# 4_Sensors.net
KiCad netlist of a schematic drawn in Altium Designer
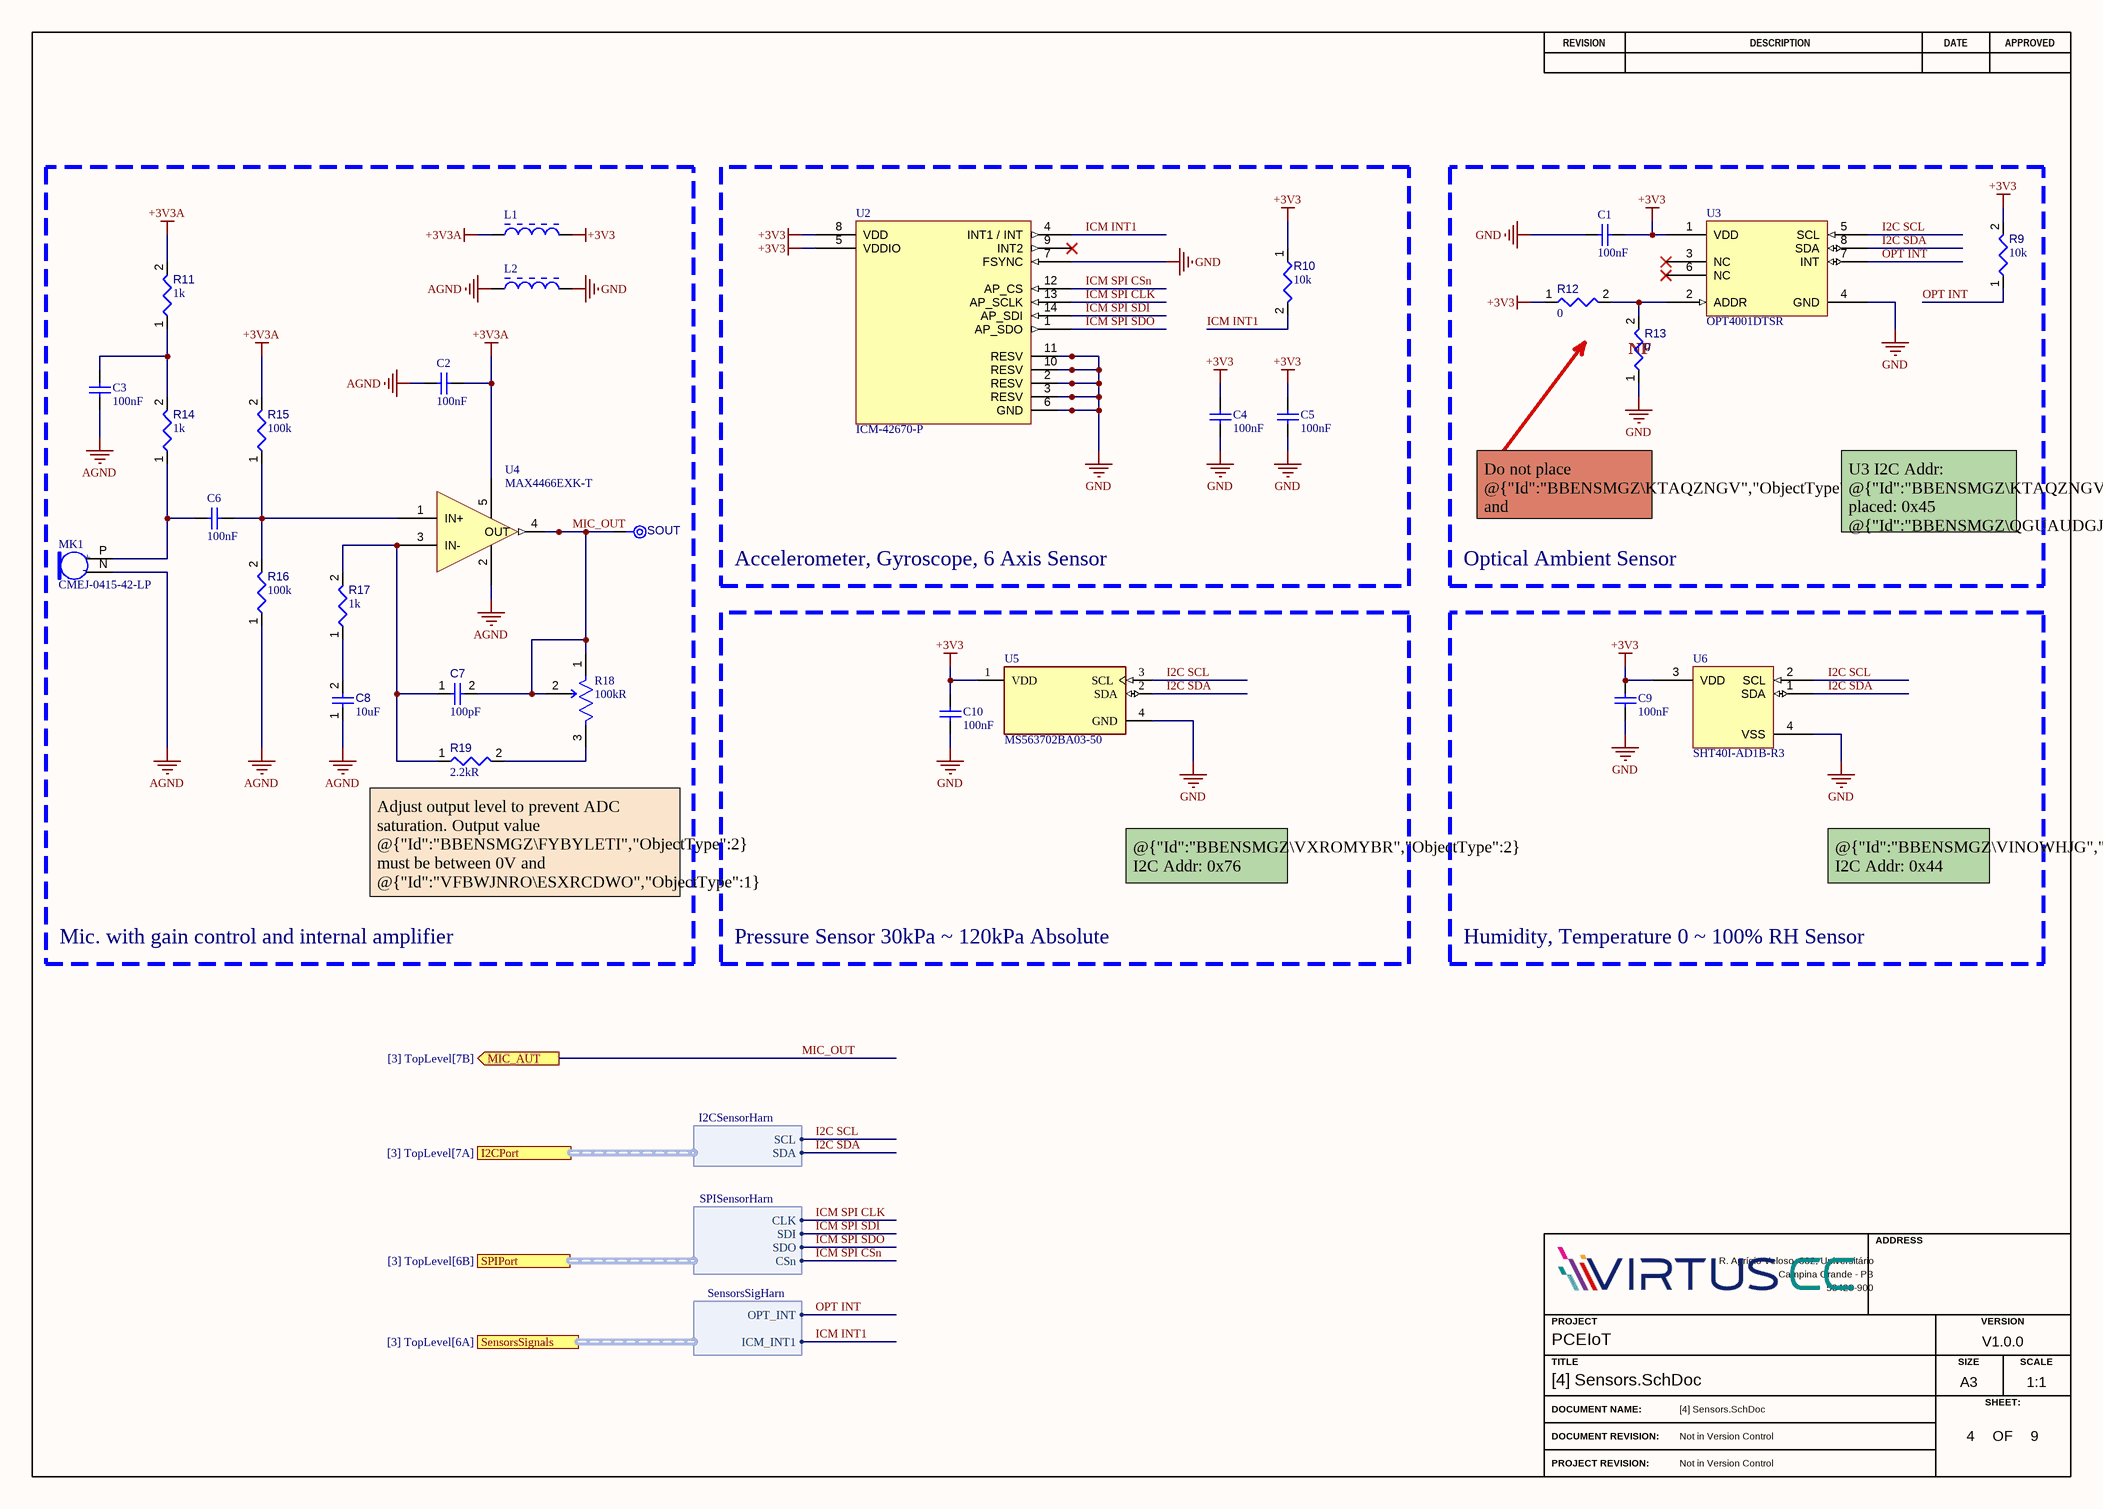
[diagram p0: [4] Sensors.SchDoc]

(export (version "E")
  (design (tool "Eeschema 10.0.6"))
  (components
    (comp (ref "C1")
      (value "100nF")
      (footprint "CAPC0603(1608)100_L")
      (description "Multilayer Ceramic Capacitor, 0.1 uF, 16 V, ± 20%, X7R, 0603 [1608 Metric]")
      (fields (field (name "TOLERANCE") "20%") (field (name "Comment") "VJ0603Y104MXJCW1BC"))
      (libsource (lib "UFCG - Universidade Federal de Campina Grande") (part "CAP"))
    )
    (comp (ref "C2")
      (value "100nF")
      (footprint "CAPC0603(1608)100_L")
      (description "Multilayer Ceramic Capacitor, 0.1 uF, 16 V, ± 20%, X7R, 0603 [1608 Metric]")
      (fields (field (name "TOLERANCE") "20%") (field (name "Comment") "VJ0603Y104MXJCW1BC"))
      (libsource (lib "UFCG - Universidade Federal de Campina Grande") (part "CAP"))
    )
    (comp (ref "C3")
      (value "100nF")
      (footprint "CAPC0603(1608)100_L")
      (description "Multilayer Ceramic Capacitor, 0.1 uF, 16 V, ± 20%, X7R, 0603 [1608 Metric]")
      (fields (field (name "TOLERANCE") "20%") (field (name "Comment") "VJ0603Y104MXJCW1BC"))
      (libsource (lib "UFCG - Universidade Federal de Campina Grande") (part "CAP"))
    )
    (comp (ref "C4")
      (value "100nF")
      (footprint "CAPC0603(1608)100_L")
      (description "Multilayer Ceramic Capacitor, 0.1 uF, 16 V, ± 20%, X7R, 0603 [1608 Metric]")
      (fields (field (name "TOLERANCE") "20%") (field (name "Comment") "VJ0603Y104MXJCW1BC"))
      (libsource (lib "UFCG - Universidade Federal de Campina Grande") (part "CAP"))
    )
    (comp (ref "C5")
      (value "100nF")
      (footprint "CAPC0603(1608)100_L")
      (description "Multilayer Ceramic Capacitor, 0.1 uF, 16 V, ± 20%, X7R, 0603 [1608 Metric]")
      (fields (field (name "TOLERANCE") "20%") (field (name "Comment") "VJ0603Y104MXJCW1BC"))
      (libsource (lib "UFCG - Universidade Federal de Campina Grande") (part "CAP"))
    )
    (comp (ref "C6")
      (value "100nF")
      (footprint "CAPC0603(1608)100_L")
      (description "Multilayer Ceramic Capacitor, 0.1 uF, 16 V, ± 20%, X7R, 0603 [1608 Metric]")
      (fields (field (name "TOLERANCE") "20%") (field (name "Comment") "VJ0603Y104MXJCW1BC"))
      (libsource (lib "UFCG - Universidade Federal de Campina Grande") (part "CAP"))
    )
    (comp (ref "C7")
      (value "100pF")
      (footprint "CAPC0603(1608)100_L")
      (description "Multilayer Ceramic Capacitor, 100 pF, 50 V, ï¿½ 10%, C0G (NP0), 0603 [1608 Metric]")
      (fields (field (name "TOLERANCE") "10%") (field (name "Comment") "C0603C101K5GACTU"))
      (libsource (lib "UFCG - Universidade Federal de Campina Grande") (part "CAP-NP-2"))
    )
    (comp (ref "C8")
      (value "10uF")
      (footprint "CAPC0603(1608)100_L")
      (description "Multilayer Ceramic Capacitor, 10 uF, 6.3 V, ± 20%, X5R, 0603 [1608 Metric]")
      (fields (field (name "TOLERANCE") "20%") (field (name "Comment") "GRM188R60J106ME47D"))
      (libsource (lib "UFCG - Universidade Federal de Campina Grande") (part "CAP-NP-2"))
    )
    (comp (ref "C9")
      (value "100nF")
      (footprint "CAPC0603(1608)100_L")
      (description "Multilayer Ceramic Capacitor, 0.1 uF, 16 V, ± 20%, X7R, 0603 [1608 Metric]")
      (fields (field (name "TOLERANCE") "20%") (field (name "Comment") "VJ0603Y104MXJCW1BC"))
      (libsource (lib "UFCG - Universidade Federal de Campina Grande") (part "CAP"))
    )
    (comp (ref "C10")
      (value "100nF")
      (footprint "CAPC0603(1608)100_L")
      (description "Multilayer Ceramic Capacitor, 0.1 uF, 16 V, ± 20%, X7R, 0603 [1608 Metric]")
      (fields (field (name "TOLERANCE") "20%") (field (name "Comment") "VJ0603Y104MXJCW1BC"))
      (libsource (lib "UFCG - Universidade Federal de Campina Grande") (part "CAP"))
    )
    (comp (ref "L1")
      (value "BLM21PG331SN1D")
      (footprint "INDC2013X105X50ML20T20")
      (fields (field (name "MANUFACTURER") "Murata") (field (name "TOLERANCE") "25%"))
      (libsource (lib "UFCG - Universidade Federal de Campina Grande") (part "IND-FB-2"))
    )
    (comp (ref "L2")
      (value "BLM21PG331SN1D")
      (footprint "INDC2013X105X50ML20T20")
      (fields (field (name "MANUFACTURER") "Murata") (field (name "TOLERANCE") "25%"))
      (libsource (lib "UFCG - Universidade Federal de Campina Grande") (part "IND-FB-2"))
    )
    (comp (ref "MK1")
      (value "CMEJ-0415-42-LP")
      (footprint "MIC_CMEJ-0415-42-LP")
      (description "4.0 mm, Omnidirectional, PCB Mount, 2.0 Vdc, Elecret Condenser Microphone")
      (fields (field (name "MF") "{'manufacturer': u'CUI'}"))
      (libsource (lib "UFCG - Universidade Federal de Campina Grande") (part "CMEJ-0415-42-LP"))
    )
    (comp (ref "R9")
      (value "10k")
      (footprint "RESC0603(1608)_L")
      (description "Chip Resistor, 10 KOhm, +/- 1%, 01 W, -55 to 155 degC, 0603 (1608 Metric)")
      (fields (field (name "POWER") "100mW") (field (name "TOLERANCE") "1%"))
      (libsource (lib "UFCG - Universidade Federal de Campina Grande") (part "RES-2"))
    )
    (comp (ref "R10")
      (value "10k")
      (footprint "RESC0603(1608)_L")
      (description "Chip Resistor, 10 KOhm, +/- 1%, 01 W, -55 to 155 degC, 0603 (1608 Metric)")
      (fields (field (name "POWER") "100mW") (field (name "TOLERANCE") "1%"))
      (libsource (lib "UFCG - Universidade Federal de Campina Grande") (part "RES-2"))
    )
    (comp (ref "R11")
      (value "1k")
      (footprint "RESC0603(1608)_L")
      (description "Chip Resistor, 1 KOhm, +/-1%, 0.1 W, -55 to 155 degC, 0603 (1608 Metric)")
      (fields (field (name "POWER") "100mW") (field (name "TOLERANCE") "1%"))
      (libsource (lib "UFCG - Universidade Federal de Campina Grande") (part "RES-2"))
    )
    (comp (ref "R12")
      (value "0")
      (footprint "RESC0603(1608)_L")
      (description "Chip Resistor, 0 Ohm, 0.1 W, -55 to 155 degC, 0603 (1608 Metric)")
      (fields (field (name "TOLERANCE") "5%") (field (name "POWER") "100mW"))
      (libsource (lib "UFCG - Universidade Federal de Campina Grande") (part "RES-2"))
    )
    (comp (ref "R13")
      (value "0")
      (footprint "RESC0603(1608)_L")
      (description "Chip Resistor, 0 Ohm, 0.1 W, -55 to 155 degC, 0603 (1608 Metric)")
      (fields (field (name "TOLERANCE") "5%") (field (name "POWER") "100mW"))
      (libsource (lib "UFCG - Universidade Federal de Campina Grande") (part "RES-2"))
    )
    (comp (ref "R14")
      (value "1k")
      (footprint "RESC0603(1608)_L")
      (description "Chip Resistor, 1 KOhm, +/-1%, 0.1 W, -55 to 155 degC, 0603 (1608 Metric)")
      (fields (field (name "POWER") "100mW") (field (name "TOLERANCE") "1%"))
      (libsource (lib "UFCG - Universidade Federal de Campina Grande") (part "RES-2"))
    )
    (comp (ref "R15")
      (value "100k")
      (footprint "RESC0603(1608)_L")
      (description "Chip Resistor, 100 KOhm, +/- 1%, 0.1 W, -55 to 155 degC, 0603 (1608 Metric)")
      (fields (field (name "TOLERANCE") "1%") (field (name "POWER") "100mW"))
      (libsource (lib "UFCG - Universidade Federal de Campina Grande") (part "RES-2"))
    )
    (comp (ref "R16")
      (value "100k")
      (footprint "RESC0603(1608)_L")
      (description "Chip Resistor, 100 KOhm, +/- 1%, 0.1 W, -55 to 155 degC, 0603 (1608 Metric)")
      (fields (field (name "TOLERANCE") "1%") (field (name "POWER") "100mW"))
      (libsource (lib "UFCG - Universidade Federal de Campina Grande") (part "RES-2"))
    )
    (comp (ref "R17")
      (value "1k")
      (footprint "RESC0603(1608)_L")
      (description "Chip Resistor, 1 KOhm, +/-1%, 0.1 W, -55 to 155 degC, 0603 (1608 Metric)")
      (fields (field (name "POWER") "100mW") (field (name "TOLERANCE") "1%"))
      (libsource (lib "UFCG - Universidade Federal de Campina Grande") (part "RES-2"))
    )
    (comp (ref "R18")
      (value "100kR")
      (footprint "FP-TC33X-2-MFG")
      (description "Cermet trimmer potentiometer, 100 kΩ, 0.1 W, SMD, on top, TC33X-2-104E")
      (fields (field (name "TOLERANCE") "25%") (field (name "Comment") "TC33X-2-104E"))
      (libsource (lib "UFCG - Universidade Federal de Campina Grande") (part "13357d81287629c2fd191d242cfa50c"))
    )
    (comp (ref "R19")
      (value "2.2kR")
      (footprint "RESC0603(1608)_L")
      (description "SMD Chip Resistor, 2.2 kOhm, ± 1%, 100 mW, 0603 [1608 Metric], Thick Film, General Purpose")
      (fields (field (name "TOLERANCE") "1%") (field (name "Comment") "CRCW06032K20FKEA"))
      (libsource (lib "UFCG - Universidade Federal de Campina Grande") (part "RES-2"))
    )
    (comp (ref "SOUT")
      (value "TPAD6R")
      (footprint "TP06R")
      (description "0.6mm round")
      (libsource (lib "PCEIOT") (part "CMP-00028-00002-2"))
    )
    (comp (ref "U2")
      (value "ICM-42670-P")
      (footprint "QFN50P300X250X81-14N")
      (description "Mems Module, 1.71-3.6 V, Lga-14 Rohs Compliant: Yes")
      (libsource (lib "UFCG - Universidade Federal de Campina Grande") (part "ICM-42670-P"))
    )
    (comp (ref "U3")
      (value "OPT4001DTSR")
      (footprint "SON50P130X60-8N")
      (description "High-speed high-precision digital ambient light sensor (ALS) 8-SOT-5X3 -40 to 85")
      (libsource (lib "UFCG - Universidade Federal de Campina Grande") (part "New symbol 1"))
    )
    (comp (ref "U4")
      (value "MAX4466EXK-T")
      (footprint "SOT65P200X110-5N")
      (description "Audio Amp Microphone 1-CH Mono Class-AB 5-Pin SC-70 T/R")
      (libsource (lib "UFCG - Universidade Federal de Campina Grande") (part "MAX4466EXK-T"))
    )
    (comp (ref "U5")
      (value "MS563702BA03-50")
      (footprint "FP-MS563702BA03-50-MFG")
      (description "Pressure Sensor, Barometric, 300 mbar, 1200 mbar, QFN, 8, -40 C")
      (libsource (lib "UFCG - Universidade Federal de Campina Grande") (part "74709a9a55dd6d6ee219151e6d8b12f"))
    )
    (comp (ref "U6")
      (value "SHT40I-AD1B-R3")
      (footprint "QFN80P150X150X55-4N")
      (description "Humidity And Temperature Sensor")
      (libsource (lib "UFCG - Universidade Federal de Campina Grande") (part "SHT40I-AD1B-R3"))
    )
  )
  (nets
    (net (code "4") (name "+3V3") (class "Default")
      (node (ref "C1") (pin "1") (pinfunction "1_1") (pintype "passive"))
      (node (ref "C10") (pin "2") (pinfunction "2_2") (pintype "passive"))
      (node (ref "C4") (pin "2") (pinfunction "2_2") (pintype "passive"))
      (node (ref "C5") (pin "2") (pinfunction "2_2") (pintype "passive"))
      (node (ref "C9") (pin "2") (pinfunction "2_2") (pintype "passive"))
      (node (ref "L1") (pin "2") (pinfunction "2_2") (pintype "passive"))
      (node (ref "R10") (pin "1") (pinfunction "1_1") (pintype "passive"))
      (node (ref "R12") (pin "1") (pinfunction "1_1") (pintype "passive"))
      (node (ref "R9") (pin "2") (pinfunction "2_2") (pintype "passive"))
      (node (ref "U2") (pin "5") (pinfunction "VDDIO_5") (pintype "power_in"))
      (node (ref "U2") (pin "8") (pinfunction "VDD_8") (pintype "power_in"))
      (node (ref "U3") (pin "1") (pinfunction "VDD_1") (pintype "power_in"))
      (node (ref "U5") (pin "1") (pinfunction "VDD_1") (pintype "power_in"))
      (node (ref "U6") (pin "3") (pinfunction "VDD_3") (pintype "power_in"))
    )
    (net (code "5") (name "+3V3A") (class "Default")
      (node (ref "C2") (pin "1") (pinfunction "1_1") (pintype "passive"))
      (node (ref "L1") (pin "1") (pinfunction "1_1") (pintype "passive"))
      (node (ref "R11") (pin "2") (pinfunction "2_2") (pintype "passive"))
      (node (ref "R15") (pin "2") (pinfunction "2_2") (pintype "passive"))
      (node (ref "U4") (pin "5") (pinfunction "VCC_5") (pintype "power_in"))
    )
    (net (code "6") (name "/I2C SCL") (class "Default")
      (node (ref "U3") (pin "5") (pinfunction "SCL_5") (pintype "input"))
      (node (ref "U5") (pin "3") (pinfunction "SCL_3") (pintype "input"))
      (node (ref "U6") (pin "2") (pinfunction "SCL_2") (pintype "input"))
    )
    (net (code "7") (name "/I2C SDA") (class "Default")
      (node (ref "U3") (pin "8") (pinfunction "SDA_8") (pintype "bidirectional"))
      (node (ref "U5") (pin "2") (pinfunction "SDA_2") (pintype "bidirectional"))
      (node (ref "U6") (pin "1") (pinfunction "SDA_1") (pintype "bidirectional"))
    )
    (net (code "8") (name "/ICM INT1") (class "Default")
      (node (ref "R10") (pin "2") (pinfunction "2_2") (pintype "passive"))
      (node (ref "U2") (pin "4") (pinfunction "INT1_/_INT_4") (pintype "output"))
    )
    (net (code "9") (name "/ICM SPI CLK") (class "Default")
      (node (ref "U2") (pin "13") (pinfunction "AP_SCLK_13") (pintype "input"))
    )
    (net (code "10") (name "/ICM SPI CSn") (class "Default")
      (node (ref "U2") (pin "12") (pinfunction "AP_CS_12") (pintype "input"))
    )
    (net (code "11") (name "/ICM SPI SDI") (class "Default")
      (node (ref "U2") (pin "14") (pinfunction "AP_SDI_14") (pintype "input"))
    )
    (net (code "12") (name "/ICM SPI SDO") (class "Default")
      (node (ref "U2") (pin "1") (pinfunction "AP_SDO_1") (pintype "output"))
    )
    (net (code "13") (name "/MIC_OUT") (class "Default")
      (node (ref "C7") (pin "2") (pinfunction "2_2") (pintype "passive"))
      (node (ref "R18") (pin "1") (pinfunction "CCW_1") (pintype "passive"))
      (node (ref "R18") (pin "2") (pinfunction "WIPER_2") (pintype "passive"))
      (node (ref "SOUT") (pin "1") (pinfunction "TP_1") (pintype "passive"))
      (node (ref "U4") (pin "4") (pinfunction "OUT_4") (pintype "output"))
    )
    (net (code "14") (name "/OPT INT") (class "Default")
      (node (ref "R9") (pin "1") (pinfunction "1_1") (pintype "passive"))
      (node (ref "U3") (pin "7") (pinfunction "INT_7") (pintype "bidirectional"))
    )
    (net (code "18") (name "AGND") (class "Default")
      (node (ref "C2") (pin "2") (pinfunction "2_2") (pintype "passive"))
      (node (ref "C3") (pin "1") (pinfunction "1_1") (pintype "passive"))
      (node (ref "C8") (pin "1") (pinfunction "1_1") (pintype "passive"))
      (node (ref "L2") (pin "1") (pinfunction "1_1") (pintype "passive"))
      (node (ref "MK1") (pin "N") (pinfunction "GND_N") (pintype "passive"))
      (node (ref "R16") (pin "1") (pinfunction "1_1") (pintype "passive"))
      (node (ref "U4") (pin "2") (pinfunction "GND_2") (pintype "power_in"))
    )
    (net (code "19") (name "GND") (class "Default")
      (node (ref "C1") (pin "2") (pinfunction "2_2") (pintype "passive"))
      (node (ref "C10") (pin "1") (pinfunction "1_1") (pintype "passive"))
      (node (ref "C4") (pin "1") (pinfunction "1_1") (pintype "passive"))
      (node (ref "C5") (pin "1") (pinfunction "1_1") (pintype "passive"))
      (node (ref "C9") (pin "1") (pinfunction "1_1") (pintype "passive"))
      (node (ref "L2") (pin "2") (pinfunction "2_2") (pintype "passive"))
      (node (ref "R13") (pin "1") (pinfunction "1_1") (pintype "passive"))
      (node (ref "U2") (pin "10") (pinfunction "RESV_10") (pintype "passive"))
      (node (ref "U2") (pin "11") (pinfunction "RESV_11") (pintype "passive"))
      (node (ref "U2") (pin "2") (pinfunction "RESV_2") (pintype "passive"))
      (node (ref "U2") (pin "3") (pinfunction "RESV_3") (pintype "passive"))
      (node (ref "U2") (pin "6") (pinfunction "GND_6") (pintype "power_in"))
      (node (ref "U2") (pin "7") (pinfunction "FSYNC_7") (pintype "input"))
      (node (ref "U3") (pin "4") (pinfunction "GND_4") (pintype "power_in"))
      (node (ref "U5") (pin "4") (pinfunction "GND_4") (pintype "power_in"))
      (node (ref "U6") (pin "4") (pinfunction "VSS_4") (pintype "power_in"))
    )
    (net (code "20") (name "Net-(C3-Pad2)") (class "Default")
      (node (ref "C3") (pin "2") (pinfunction "2_2") (pintype "passive"))
      (node (ref "R11") (pin "1") (pinfunction "1_1") (pintype "passive"))
      (node (ref "R14") (pin "2") (pinfunction "2_2") (pintype "passive"))
    )
    (net (code "21") (name "Net-(C8-Pad2)") (class "Default")
      (node (ref "C8") (pin "2") (pinfunction "2_2") (pintype "passive"))
      (node (ref "R17") (pin "1") (pinfunction "1_1") (pintype "passive"))
    )
    (net (code "22") (name "Net-(MK1-OUTPUT)") (class "Default")
      (node (ref "C6") (pin "2") (pinfunction "2_2") (pintype "passive"))
      (node (ref "MK1") (pin "P") (pinfunction "OUTPUT_P") (pintype "passive"))
      (node (ref "R14") (pin "1") (pinfunction "1_1") (pintype "passive"))
    )
    (net (code "23") (name "Net-(R18-CW)") (class "Default")
      (node (ref "R18") (pin "3") (pinfunction "CW_3") (pintype "passive"))
      (node (ref "R19") (pin "2") (pinfunction "2_2") (pintype "passive"))
    )
    (net (code "24") (name "Net-(U3-ADDR)") (class "Default")
      (node (ref "R12") (pin "2") (pinfunction "2_2") (pintype "passive"))
      (node (ref "R13") (pin "2") (pinfunction "2_2") (pintype "passive"))
      (node (ref "U3") (pin "2") (pinfunction "ADDR_2") (pintype "input"))
    )
    (net (code "25") (name "Net-(U4-IN+)") (class "Default")
      (node (ref "C6") (pin "1") (pinfunction "1_1") (pintype "passive"))
      (node (ref "R15") (pin "1") (pinfunction "1_1") (pintype "passive"))
      (node (ref "R16") (pin "2") (pinfunction "2_2") (pintype "passive"))
      (node (ref "U4") (pin "1") (pinfunction "IN+_1") (pintype "passive"))
    )
    (net (code "26") (name "Net-(U4-IN-)") (class "Default")
      (node (ref "C7") (pin "1") (pinfunction "1_1") (pintype "passive"))
      (node (ref "R17") (pin "2") (pinfunction "2_2") (pintype "passive"))
      (node (ref "R19") (pin "1") (pinfunction "1_1") (pintype "passive"))
      (node (ref "U4") (pin "3") (pinfunction "IN-_3") (pintype "passive"))
    )
    (net (code "27") (name "unconnected-(U2-INT2-Pad9)") (class "Default")
      (node (ref "U2") (pin "9") (pinfunction "INT2_9") (pintype "output+no_connect"))
    )
    (net (code "28") (name "unconnected-(U3-NC-Pad3)") (class "Default")
      (node (ref "U3") (pin "3") (pinfunction "NC_3") (pintype "passive+no_connect"))
    )
    (net (code "29") (name "unconnected-(U3-NC-Pad6)") (class "Default")
      (node (ref "U3") (pin "6") (pinfunction "NC_6") (pintype "passive+no_connect"))
    )
  )
)
